# 7Seg.net
KiCad netlist of a schematic drawn in Altium Designer
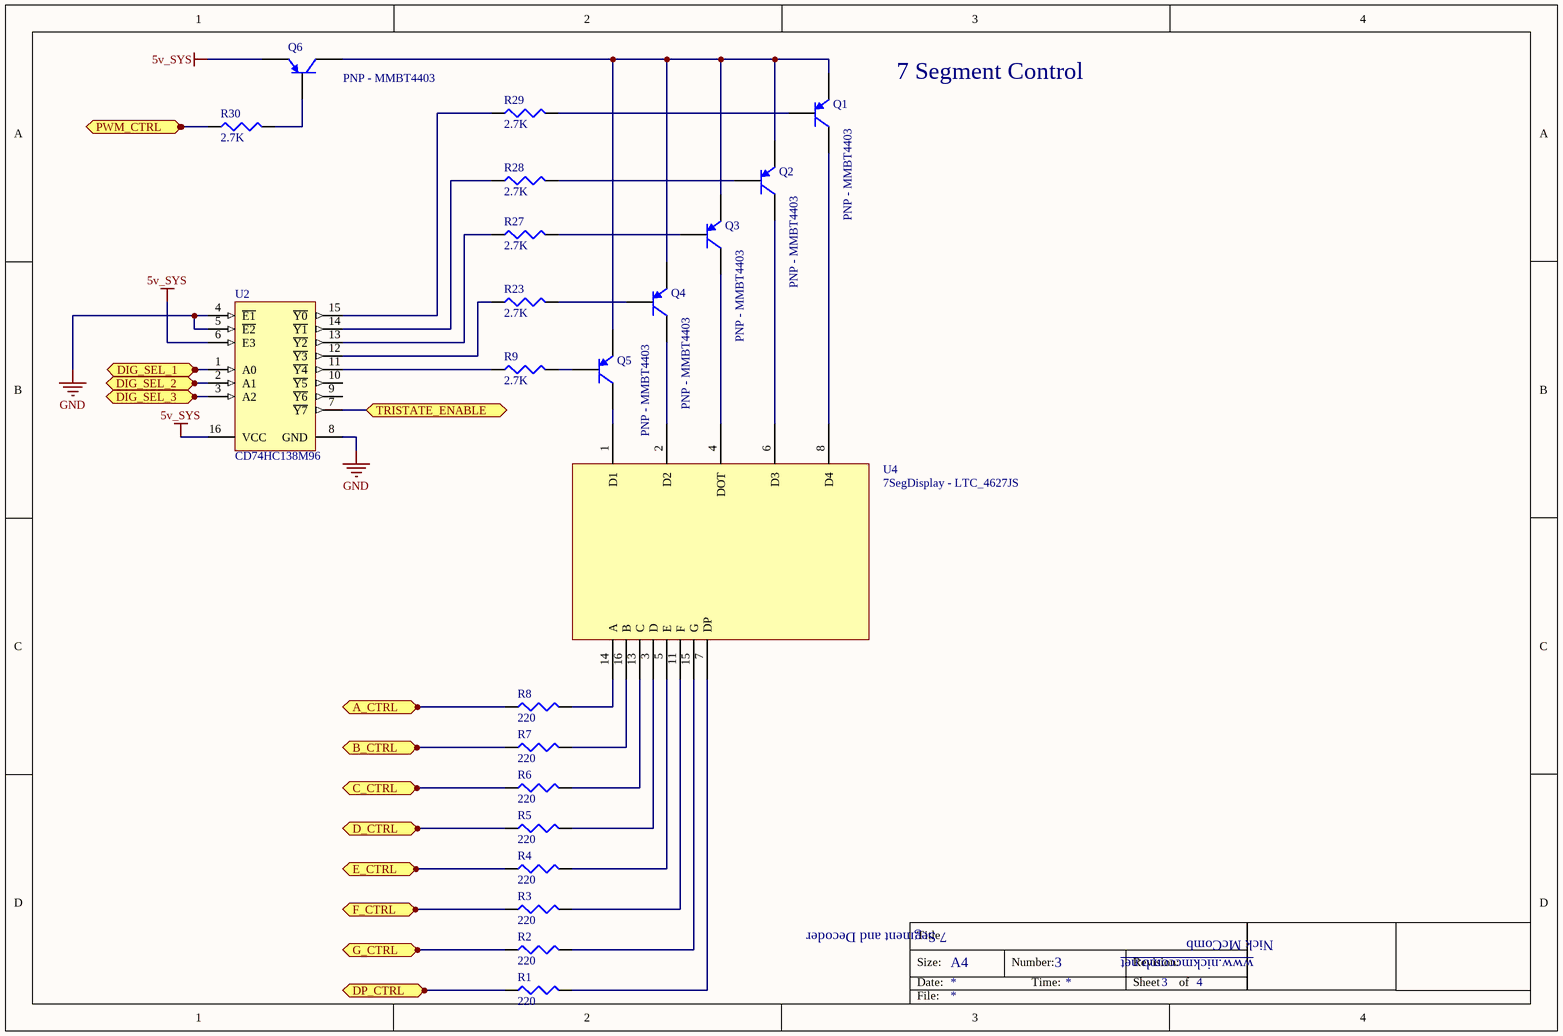
[diagram p0: 7Seg.SchDoc]

(export (version "E")
  (design (tool "Eeschema 10.0.6"))
  (components
    (comp (ref "Q1")
      (value "PNP - MMBT4403")
      (footprint "TO-92A - BJT")
      (description "PNP Bipolar Transistor")
      (libsource (lib "lab2") (part "PNP - MMBT4403"))
    )
    (comp (ref "Q2")
      (value "PNP - MMBT4403")
      (footprint "TO-92A - BJT")
      (description "PNP Bipolar Transistor")
      (libsource (lib "lab2") (part "PNP - MMBT4403"))
    )
    (comp (ref "Q3")
      (value "PNP - MMBT4403")
      (footprint "TO-92A - BJT")
      (description "PNP Bipolar Transistor")
      (libsource (lib "lab2") (part "PNP - MMBT4403"))
    )
    (comp (ref "Q4")
      (value "PNP - MMBT4403")
      (footprint "TO-92A - BJT")
      (description "PNP Bipolar Transistor")
      (libsource (lib "lab2") (part "PNP - MMBT4403"))
    )
    (comp (ref "Q5")
      (value "PNP - MMBT4403")
      (footprint "TO-92A - BJT")
      (description "PNP Bipolar Transistor")
      (libsource (lib "lab2") (part "PNP - MMBT4403"))
    )
    (comp (ref "Q6")
      (value "PNP - MMBT4403")
      (footprint "TO-92A - BJT")
      (description "PNP Bipolar Transistor")
      (libsource (lib "lab2") (part "PNP - MMBT4403"))
    )
    (comp (ref "R1")
      (value "220")
      (footprint "J1-0603")
      (description "Resistor")
      (fields (field (name "PUBLISHER") "Altium Limited"))
      (libsource (lib "lab2") (part "Res3"))
    )
    (comp (ref "R2")
      (value "220")
      (footprint "J1-0603")
      (description "Resistor")
      (fields (field (name "PUBLISHER") "Altium Limited"))
      (libsource (lib "lab2") (part "Res3"))
    )
    (comp (ref "R3")
      (value "220")
      (footprint "J1-0603")
      (description "Resistor")
      (fields (field (name "PUBLISHER") "Altium Limited"))
      (libsource (lib "lab2") (part "Res3"))
    )
    (comp (ref "R4")
      (value "220")
      (footprint "J1-0603")
      (description "Resistor")
      (fields (field (name "PUBLISHER") "Altium Limited"))
      (libsource (lib "lab2") (part "Res3"))
    )
    (comp (ref "R5")
      (value "220")
      (footprint "J1-0603")
      (description "Resistor")
      (fields (field (name "PUBLISHER") "Altium Limited"))
      (libsource (lib "lab2") (part "Res3"))
    )
    (comp (ref "R6")
      (value "220")
      (footprint "J1-0603")
      (description "Resistor")
      (fields (field (name "PUBLISHER") "Altium Limited"))
      (libsource (lib "lab2") (part "Res3"))
    )
    (comp (ref "R7")
      (value "220")
      (footprint "J1-0603")
      (description "Resistor")
      (fields (field (name "PUBLISHER") "Altium Limited"))
      (libsource (lib "lab2") (part "Res3"))
    )
    (comp (ref "R8")
      (value "220")
      (footprint "J1-0603")
      (description "Resistor")
      (fields (field (name "PUBLISHER") "Altium Limited"))
      (libsource (lib "lab2") (part "Res3"))
    )
    (comp (ref "R9")
      (value "2.7K")
      (footprint "J1-0603")
      (description "Resistor")
      (fields (field (name "PUBLISHER") "Altium Limited"))
      (libsource (lib "lab2") (part "Res3"))
    )
    (comp (ref "R23")
      (value "2.7K")
      (footprint "J1-0603")
      (description "Resistor")
      (fields (field (name "PUBLISHER") "Altium Limited"))
      (libsource (lib "lab2") (part "Res3"))
    )
    (comp (ref "R27")
      (value "2.7K")
      (footprint "J1-0603")
      (description "Resistor")
      (fields (field (name "PUBLISHER") "Altium Limited"))
      (libsource (lib "lab2") (part "Res3"))
    )
    (comp (ref "R28")
      (value "2.7K")
      (footprint "J1-0603")
      (description "Resistor")
      (fields (field (name "PUBLISHER") "Altium Limited"))
      (libsource (lib "lab2") (part "Res3"))
    )
    (comp (ref "R29")
      (value "2.7K")
      (footprint "J1-0603")
      (description "Resistor")
      (fields (field (name "PUBLISHER") "Altium Limited"))
      (libsource (lib "lab2") (part "Res3"))
    )
    (comp (ref "R30")
      (value "2.7K")
      (footprint "J1-0603")
      (description "Resistor")
      (fields (field (name "PUBLISHER") "Altium Limited"))
      (libsource (lib "lab2") (part "Res3"))
    )
    (comp (ref "U2")
      (value "CD74HC138M96")
      (footprint "D0016A_L")
      (fields
        (field (name "GENERIC PART NUMBER") "CD74HC138")
        (field (name "MANUFACTURER") "Texas Instruments")
      )
      (libsource (lib "Altium Content Vault") (part "TI-CDX4HCT138-16"))
    )
    (comp (ref "U4") (value "7SegDisplay - LTC_4627JS") (libsource (lib "lab2") (part "7SegDisplay")))
  )
  (nets
    (net (code "1") (name "/A_CTRL") (class "Default")
      (node (ref "R8") (pin "1") (pinfunction "1_1") (pintype "passive"))
    )
    (net (code "2") (name "/B_CTRL") (class "Default")
      (node (ref "R7") (pin "1") (pinfunction "1_1") (pintype "passive"))
    )
    (net (code "3") (name "/C_CTRL") (class "Default")
      (node (ref "R6") (pin "1") (pinfunction "1_1") (pintype "passive"))
    )
    (net (code "4") (name "/DIG_SEL_1") (class "Default")
      (node (ref "U2") (pin "1") (pinfunction "A0_1") (pintype "input"))
    )
    (net (code "5") (name "/DIG_SEL_2") (class "Default")
      (node (ref "U2") (pin "2") (pinfunction "A1_2") (pintype "input"))
    )
    (net (code "6") (name "/DIG_SEL_3") (class "Default")
      (node (ref "U2") (pin "3") (pinfunction "A2_3") (pintype "input"))
    )
    (net (code "7") (name "/DP_CTRL") (class "Default")
      (node (ref "R1") (pin "1") (pinfunction "1_1") (pintype "passive"))
    )
    (net (code "8") (name "/D_CTRL") (class "Default")
      (node (ref "R5") (pin "1") (pinfunction "1_1") (pintype "passive"))
    )
    (net (code "9") (name "/E_CTRL") (class "Default")
      (node (ref "R4") (pin "1") (pinfunction "1_1") (pintype "passive"))
    )
    (net (code "10") (name "/F_CTRL") (class "Default")
      (node (ref "R3") (pin "1") (pinfunction "1_1") (pintype "passive"))
    )
    (net (code "11") (name "/G_CTRL") (class "Default")
      (node (ref "R2") (pin "1") (pinfunction "1_1") (pintype "passive"))
    )
    (net (code "12") (name "/PWM_CTRL") (class "Default")
      (node (ref "R30") (pin "1") (pinfunction "1_1") (pintype "passive"))
    )
    (net (code "13") (name "/TRISTATE_ENABLE") (class "Default")
      (node (ref "U2") (pin "7") (pinfunction "~{Y7}_7") (pintype "output"))
    )
    (net (code "14") (name "5v_SYS") (class "Default")
      (node (ref "Q6") (pin "3") (pinfunction "E_3") (pintype "passive"))
      (node (ref "U2") (pin "16") (pinfunction "VCC_16") (pintype "power_in"))
      (node (ref "U2") (pin "6") (pinfunction "E3_6") (pintype "input"))
    )
    (net (code "15") (name "GND") (class "Default")
      (node (ref "U2") (pin "4") (pinfunction "~{E1}_4") (pintype "input"))
      (node (ref "U2") (pin "5") (pinfunction "~{E2}_5") (pintype "input"))
      (node (ref "U2") (pin "8") (pinfunction "GND_8") (pintype "power_in"))
    )
    (net (code "16") (name "Net-(Q1-B)") (class "Default")
      (node (ref "Q1") (pin "2") (pinfunction "B_2") (pintype "passive"))
      (node (ref "R29") (pin "2") (pinfunction "2_2") (pintype "passive"))
    )
    (net (code "17") (name "Net-(Q1-C)") (class "Default")
      (node (ref "Q1") (pin "1") (pinfunction "C_1") (pintype "passive"))
      (node (ref "U4") (pin "8") (pinfunction "D4_8") (pintype "passive"))
    )
    (net (code "18") (name "Net-(Q1-E)") (class "Default")
      (node (ref "Q1") (pin "3") (pinfunction "E_3") (pintype "passive"))
      (node (ref "Q2") (pin "3") (pinfunction "E_3") (pintype "passive"))
      (node (ref "Q3") (pin "3") (pinfunction "E_3") (pintype "passive"))
      (node (ref "Q4") (pin "3") (pinfunction "E_3") (pintype "passive"))
      (node (ref "Q5") (pin "3") (pinfunction "E_3") (pintype "passive"))
      (node (ref "Q6") (pin "1") (pinfunction "C_1") (pintype "passive"))
    )
    (net (code "19") (name "Net-(Q2-B)") (class "Default")
      (node (ref "Q2") (pin "2") (pinfunction "B_2") (pintype "passive"))
      (node (ref "R28") (pin "2") (pinfunction "2_2") (pintype "passive"))
    )
    (net (code "20") (name "Net-(Q2-C)") (class "Default")
      (node (ref "Q2") (pin "1") (pinfunction "C_1") (pintype "passive"))
      (node (ref "U4") (pin "6") (pinfunction "D3_6") (pintype "passive"))
    )
    (net (code "21") (name "Net-(Q3-B)") (class "Default")
      (node (ref "Q3") (pin "2") (pinfunction "B_2") (pintype "passive"))
      (node (ref "R27") (pin "2") (pinfunction "2_2") (pintype "passive"))
    )
    (net (code "22") (name "Net-(Q3-C)") (class "Default")
      (node (ref "Q3") (pin "1") (pinfunction "C_1") (pintype "passive"))
      (node (ref "U4") (pin "4") (pinfunction "DOT_4") (pintype "passive"))
    )
    (net (code "23") (name "Net-(Q4-B)") (class "Default")
      (node (ref "Q4") (pin "2") (pinfunction "B_2") (pintype "passive"))
      (node (ref "R23") (pin "2") (pinfunction "2_2") (pintype "passive"))
    )
    (net (code "24") (name "Net-(Q4-C)") (class "Default")
      (node (ref "Q4") (pin "1") (pinfunction "C_1") (pintype "passive"))
      (node (ref "U4") (pin "2") (pinfunction "D2_2") (pintype "passive"))
    )
    (net (code "25") (name "Net-(Q5-B)") (class "Default")
      (node (ref "Q5") (pin "2") (pinfunction "B_2") (pintype "passive"))
      (node (ref "R9") (pin "2") (pinfunction "2_2") (pintype "passive"))
    )
    (net (code "26") (name "Net-(Q5-C)") (class "Default")
      (node (ref "Q5") (pin "1") (pinfunction "C_1") (pintype "passive"))
      (node (ref "U4") (pin "1") (pinfunction "D1_1") (pintype "passive"))
    )
    (net (code "27") (name "Net-(Q6-B)") (class "Default")
      (node (ref "Q6") (pin "2") (pinfunction "B_2") (pintype "passive"))
      (node (ref "R30") (pin "2") (pinfunction "2_2") (pintype "passive"))
    )
    (net (code "28") (name "Net-(U2-~{Y0})") (class "Default")
      (node (ref "R29") (pin "1") (pinfunction "1_1") (pintype "passive"))
      (node (ref "U2") (pin "15") (pinfunction "~{Y0}_15") (pintype "output"))
    )
    (net (code "29") (name "Net-(U2-~{Y1})") (class "Default")
      (node (ref "R28") (pin "1") (pinfunction "1_1") (pintype "passive"))
      (node (ref "U2") (pin "14") (pinfunction "~{Y1}_14") (pintype "output"))
    )
    (net (code "30") (name "Net-(U2-~{Y2})") (class "Default")
      (node (ref "R27") (pin "1") (pinfunction "1_1") (pintype "passive"))
      (node (ref "U2") (pin "13") (pinfunction "~{Y2}_13") (pintype "output"))
    )
    (net (code "31") (name "Net-(U2-~{Y3})") (class "Default")
      (node (ref "R23") (pin "1") (pinfunction "1_1") (pintype "passive"))
      (node (ref "U2") (pin "12") (pinfunction "~{Y3}_12") (pintype "output"))
    )
    (net (code "32") (name "Net-(U2-~{Y4})") (class "Default")
      (node (ref "R9") (pin "1") (pinfunction "1_1") (pintype "passive"))
      (node (ref "U2") (pin "11") (pinfunction "~{Y4}_11") (pintype "output"))
    )
    (net (code "33") (name "Net-(U4-A)") (class "Default")
      (node (ref "R8") (pin "2") (pinfunction "2_2") (pintype "passive"))
      (node (ref "U4") (pin "14") (pinfunction "A_14") (pintype "passive"))
    )
    (net (code "34") (name "Net-(U4-B)") (class "Default")
      (node (ref "R7") (pin "2") (pinfunction "2_2") (pintype "passive"))
      (node (ref "U4") (pin "16") (pinfunction "B_16") (pintype "passive"))
    )
    (net (code "35") (name "Net-(U4-C)") (class "Default")
      (node (ref "R6") (pin "2") (pinfunction "2_2") (pintype "passive"))
      (node (ref "U4") (pin "13") (pinfunction "C_13") (pintype "passive"))
    )
    (net (code "36") (name "Net-(U4-D)") (class "Default")
      (node (ref "R5") (pin "2") (pinfunction "2_2") (pintype "passive"))
      (node (ref "U4") (pin "3") (pinfunction "D_3") (pintype "passive"))
    )
    (net (code "37") (name "Net-(U4-DP)") (class "Default")
      (node (ref "R1") (pin "2") (pinfunction "2_2") (pintype "passive"))
      (node (ref "U4") (pin "7") (pinfunction "DP_7") (pintype "passive"))
    )
    (net (code "38") (name "Net-(U4-E)") (class "Default")
      (node (ref "R4") (pin "2") (pinfunction "2_2") (pintype "passive"))
      (node (ref "U4") (pin "5") (pinfunction "E_5") (pintype "passive"))
    )
    (net (code "39") (name "Net-(U4-F)") (class "Default")
      (node (ref "R3") (pin "2") (pinfunction "2_2") (pintype "passive"))
      (node (ref "U4") (pin "11") (pinfunction "F_11") (pintype "passive"))
    )
    (net (code "40") (name "Net-(U4-G)") (class "Default")
      (node (ref "R2") (pin "2") (pinfunction "2_2") (pintype "passive"))
      (node (ref "U4") (pin "15") (pinfunction "G_15") (pintype "passive"))
    )
    (net (code "41") (name "unconnected-(U2-~{Y5}-Pad10)") (class "Default")
      (node (ref "U2") (pin "10") (pinfunction "~{Y5}_10") (pintype "output"))
    )
    (net (code "42") (name "unconnected-(U2-~{Y6}-Pad9)") (class "Default")
      (node (ref "U2") (pin "9") (pinfunction "~{Y6}_9") (pintype "output"))
    )
  )
)
